# Power.net
KiCad netlist of a schematic drawn in Altium Designer
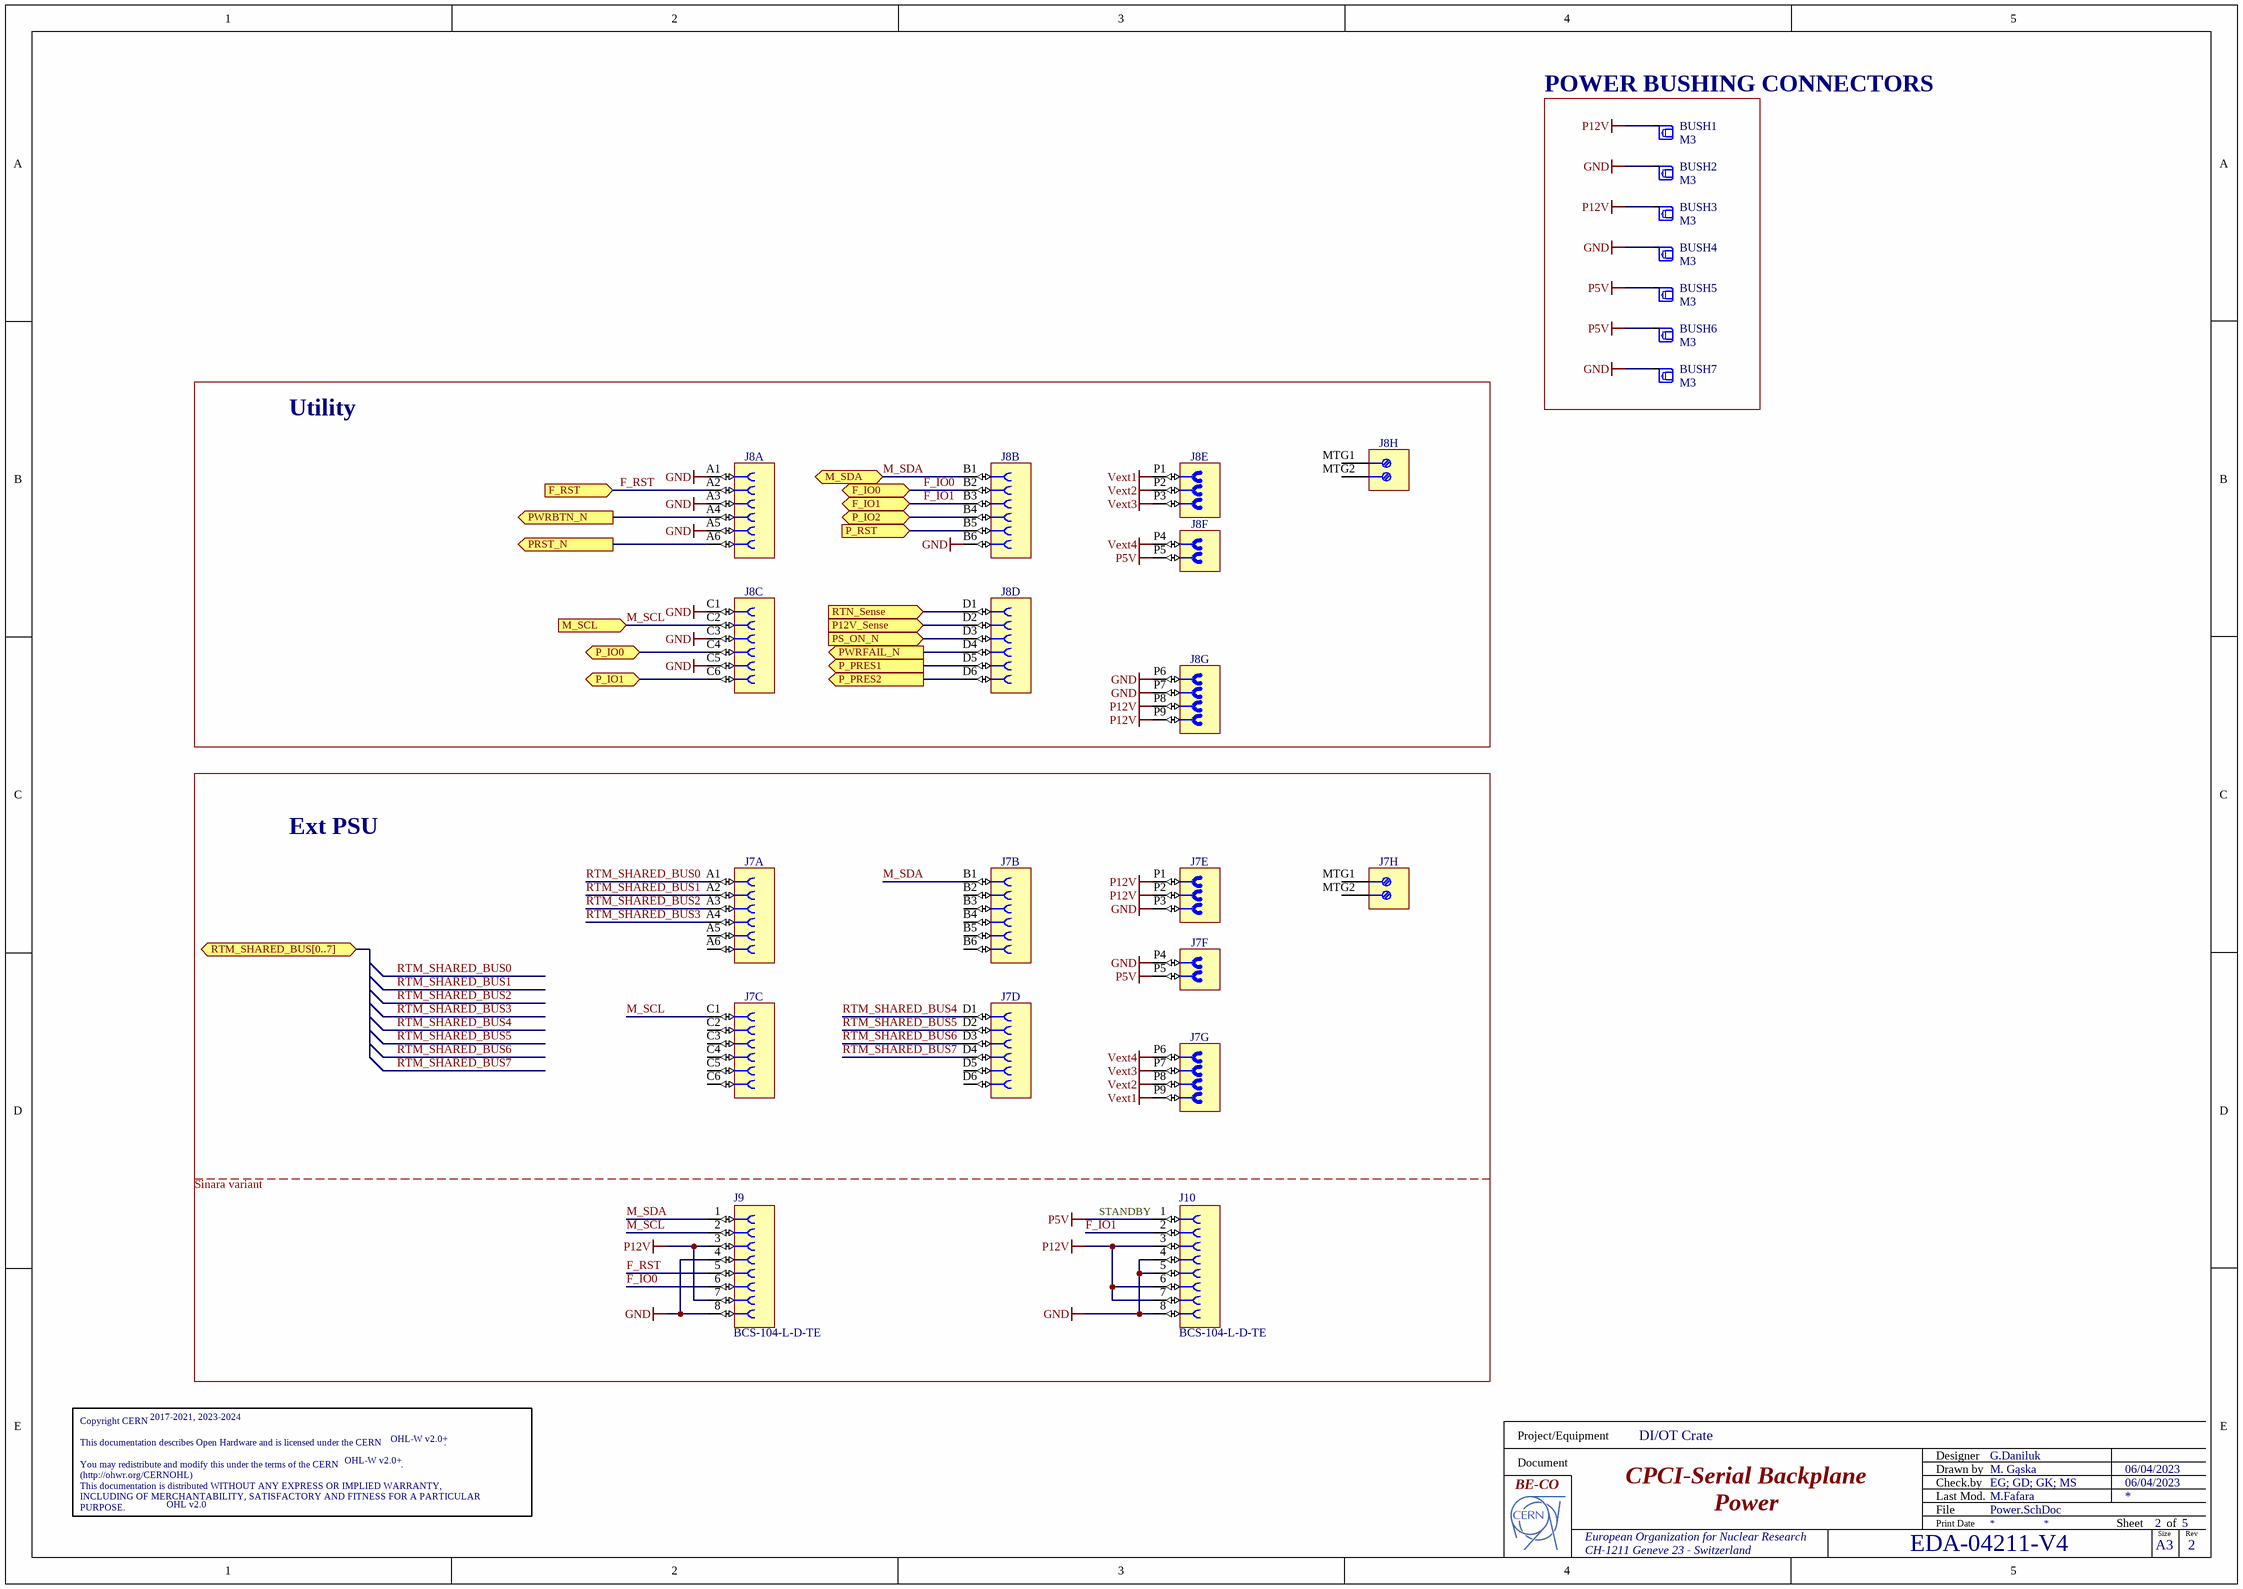
[diagram p0: Power.SchDoc]

(export (version "E")
  (design (tool "Eeschema 10.0.6"))
  (components
    (comp (ref "BUSH1")
      (value "M3")
      (footprint "WURTH_7461057")
      (description "Bush")
      (fields
        (field (name "PART NUMBER") "WURTH_7461057")
        (field (name "MANUFACTURER") "WURTH")
        (field (name "AUTHOR") "CERN DEM JLC")
      )
      (libsource (lib "Eletro-mechanical") (part "Bush"))
    )
    (comp (ref "BUSH2")
      (value "M3")
      (footprint "WURTH_7461057")
      (description "Bush")
      (fields
        (field (name "PART NUMBER") "WURTH_7461057")
        (field (name "MANUFACTURER") "WURTH")
        (field (name "AUTHOR") "CERN DEM JLC")
      )
      (libsource (lib "Eletro-mechanical") (part "Bush"))
    )
    (comp (ref "BUSH3")
      (value "M3")
      (footprint "WURTH_7461057")
      (description "Bush")
      (fields
        (field (name "PART NUMBER") "WURTH_7461057")
        (field (name "MANUFACTURER") "WURTH")
        (field (name "AUTHOR") "CERN DEM JLC")
      )
      (libsource (lib "Eletro-mechanical") (part "Bush"))
    )
    (comp (ref "BUSH4")
      (value "M3")
      (footprint "WURTH_7461057")
      (description "Bush")
      (fields
        (field (name "PART NUMBER") "WURTH_7461057")
        (field (name "MANUFACTURER") "WURTH")
        (field (name "AUTHOR") "CERN DEM JLC")
      )
      (libsource (lib "Eletro-mechanical") (part "Bush"))
    )
    (comp (ref "BUSH5")
      (value "M3")
      (footprint "WURTH_7461057")
      (description "Bush")
      (fields
        (field (name "PART NUMBER") "WURTH_7461057")
        (field (name "MANUFACTURER") "WURTH")
        (field (name "AUTHOR") "CERN DEM JLC")
      )
      (libsource (lib "Eletro-mechanical") (part "Bush"))
    )
    (comp (ref "BUSH6")
      (value "M3")
      (footprint "WURTH_7461057")
      (description "Bush")
      (fields
        (field (name "PART NUMBER") "WURTH_7461057")
        (field (name "MANUFACTURER") "WURTH")
        (field (name "AUTHOR") "CERN DEM JLC")
      )
      (libsource (lib "Eletro-mechanical") (part "Bush"))
    )
    (comp (ref "BUSH7")
      (value "M3")
      (footprint "WURTH_7461057")
      (description "Bush")
      (fields
        (field (name "PART NUMBER") "WURTH_7461057")
        (field (name "MANUFACTURER") "WURTH")
        (field (name "AUTHOR") "CERN DEM JLC")
      )
      (libsource (lib "Eletro-mechanical") (part "Bush"))
    )
    (comp (ref "J7")
      (value "PwrBlade")
      (footprint "AMPHENOL_51940-650")
      (description "Thru-Hole, Lead 3.43mm, PowerBlade Vertical Power Connector 3ACP 2P 24S 4DCP Contacts")
      (fields
        (field (name "PART NUMBER") "AMPHENOL_51940-650")
        (field (name "MANUFACTURER") "AMPHENOL")
        (field (name "AUTHOR") "CERN DEM HF")
      )
      (libsource (lib "Connectors") (part "AMPHENOL_51940-650"))
    )
    (comp (ref "J8")
      (value "PwrBlade")
      (footprint "AMPHENOL_51940-650")
      (description "Thru-Hole, Lead 3.43mm, PowerBlade Vertical Power Connector 3ACP 2P 24S 4DCP Contacts")
      (fields
        (field (name "PART NUMBER") "AMPHENOL_51940-650")
        (field (name "MANUFACTURER") "AMPHENOL")
        (field (name "AUTHOR") "CERN DEM HF")
      )
      (libsource (lib "Connectors") (part "AMPHENOL_51940-650"))
    )
    (comp (ref "J9")
      (value "BCS-104-L-D-TE")
      (footprint "SAMTEC_BCS-104-L-D-TE")
      (libsource (lib "TechnoSystem Workspace") (part "8 pin female"))
    )
    (comp (ref "J10")
      (value "BCS-104-L-D-TE")
      (footprint "SAMTEC_BCS-104-L-D-TE")
      (libsource (lib "TechnoSystem Workspace") (part "8 pin female"))
    )
  )
  (nets
    (net (code "1") (name "/F_IO0") (class "Default")
      (node (ref "J8") (pin "B2") (pinfunction "B2_B2") (pintype "bidirectional"))
      (node (ref "J9") (pin "6") (pinfunction "6_6") (pintype "bidirectional"))
    )
    (net (code "2") (name "/F_IO1") (class "Default")
      (node (ref "J10") (pin "2") (pinfunction "2_2") (pintype "bidirectional"))
      (node (ref "J8") (pin "B3") (pinfunction "B3_B3") (pintype "bidirectional"))
    )
    (net (code "3") (name "/F_RST") (class "Default")
      (node (ref "J8") (pin "A2") (pinfunction "A2_A2") (pintype "bidirectional"))
      (node (ref "J9") (pin "5") (pinfunction "5_5") (pintype "bidirectional"))
    )
    (net (code "4") (name "/M_SCL") (class "Default")
      (node (ref "J7") (pin "C1") (pinfunction "C1_C1") (pintype "bidirectional"))
      (node (ref "J8") (pin "C2") (pinfunction "C2_C2") (pintype "bidirectional"))
      (node (ref "J9") (pin "2") (pinfunction "2_2") (pintype "bidirectional"))
    )
    (net (code "5") (name "/M_SDA") (class "Default")
      (node (ref "J7") (pin "B1") (pinfunction "B1_B1") (pintype "bidirectional"))
      (node (ref "J8") (pin "B1") (pinfunction "B1_B1") (pintype "bidirectional"))
      (node (ref "J9") (pin "1") (pinfunction "1_1") (pintype "bidirectional"))
    )
    (net (code "6") (name "/P12V_Sense") (class "Default")
      (node (ref "J8") (pin "D2") (pinfunction "D2_D2") (pintype "bidirectional"))
    )
    (net (code "7") (name "/PRST_N") (class "Default")
      (node (ref "J8") (pin "A6") (pinfunction "A6_A6") (pintype "bidirectional"))
    )
    (net (code "8") (name "/PS_ON_N") (class "Default")
      (node (ref "J8") (pin "D3") (pinfunction "D3_D3") (pintype "bidirectional"))
    )
    (net (code "9") (name "/PWRBTN_N") (class "Default")
      (node (ref "J8") (pin "A4") (pinfunction "A4_A4") (pintype "bidirectional"))
    )
    (net (code "10") (name "/PWRFAIL_N") (class "Default")
      (node (ref "J8") (pin "D4") (pinfunction "D4_D4") (pintype "bidirectional"))
    )
    (net (code "11") (name "/P_IO0") (class "Default")
      (node (ref "J8") (pin "C4") (pinfunction "C4_C4") (pintype "bidirectional"))
    )
    (net (code "12") (name "/P_IO1") (class "Default")
      (node (ref "J8") (pin "C6") (pinfunction "C6_C6") (pintype "bidirectional"))
    )
    (net (code "13") (name "/P_IO2") (class "Default")
      (node (ref "J8") (pin "B4") (pinfunction "B4_B4") (pintype "bidirectional"))
    )
    (net (code "14") (name "/P_PRES1") (class "Default")
      (node (ref "J8") (pin "D5") (pinfunction "D5_D5") (pintype "bidirectional"))
    )
    (net (code "15") (name "/P_PRES2") (class "Default")
      (node (ref "J8") (pin "D6") (pinfunction "D6_D6") (pintype "bidirectional"))
    )
    (net (code "16") (name "/P_RST") (class "Default")
      (node (ref "J8") (pin "B5") (pinfunction "B5_B5") (pintype "bidirectional"))
    )
    (net (code "17") (name "/RTM_SHARED_BUS0") (class "Default")
      (node (ref "J7") (pin "A1") (pinfunction "A1_A1") (pintype "bidirectional"))
    )
    (net (code "18") (name "/RTM_SHARED_BUS1") (class "Default")
      (node (ref "J7") (pin "A2") (pinfunction "A2_A2") (pintype "bidirectional"))
    )
    (net (code "19") (name "/RTM_SHARED_BUS2") (class "Default")
      (node (ref "J7") (pin "A3") (pinfunction "A3_A3") (pintype "bidirectional"))
    )
    (net (code "20") (name "/RTM_SHARED_BUS3") (class "Default")
      (node (ref "J7") (pin "A4") (pinfunction "A4_A4") (pintype "bidirectional"))
    )
    (net (code "21") (name "/RTM_SHARED_BUS4") (class "Default")
      (node (ref "J7") (pin "D1") (pinfunction "D1_D1") (pintype "bidirectional"))
    )
    (net (code "22") (name "/RTM_SHARED_BUS5") (class "Default")
      (node (ref "J7") (pin "D2") (pinfunction "D2_D2") (pintype "bidirectional"))
    )
    (net (code "23") (name "/RTM_SHARED_BUS6") (class "Default")
      (node (ref "J7") (pin "D3") (pinfunction "D3_D3") (pintype "bidirectional"))
    )
    (net (code "24") (name "/RTM_SHARED_BUS7") (class "Default")
      (node (ref "J7") (pin "D4") (pinfunction "D4_D4") (pintype "bidirectional"))
    )
    (net (code "26") (name "/RTN_Sense") (class "Default")
      (node (ref "J8") (pin "D1") (pinfunction "D1_D1") (pintype "bidirectional"))
    )
    (net (code "27") (name "GND") (class "Default")
      (node (ref "BUSH2") (pin "1") (pinfunction "1_1") (pintype "bidirectional"))
      (node (ref "BUSH4") (pin "1") (pinfunction "1_1") (pintype "bidirectional"))
      (node (ref "BUSH7") (pin "1") (pinfunction "1_1") (pintype "bidirectional"))
      (node (ref "J10") (pin "4") (pinfunction "4_4") (pintype "bidirectional"))
      (node (ref "J10") (pin "5") (pinfunction "5_5") (pintype "bidirectional"))
      (node (ref "J10") (pin "8") (pinfunction "8_8") (pintype "bidirectional"))
      (node (ref "J7") (pin "P3") (pinfunction "P3_P3") (pintype "bidirectional"))
      (node (ref "J7") (pin "P4") (pinfunction "P4_P4") (pintype "bidirectional"))
      (node (ref "J8") (pin "A1") (pinfunction "A1_A1") (pintype "bidirectional"))
      (node (ref "J8") (pin "A3") (pinfunction "A3_A3") (pintype "bidirectional"))
      (node (ref "J8") (pin "A5") (pinfunction "A5_A5") (pintype "bidirectional"))
      (node (ref "J8") (pin "B6") (pinfunction "B6_B6") (pintype "bidirectional"))
      (node (ref "J8") (pin "C1") (pinfunction "C1_C1") (pintype "bidirectional"))
      (node (ref "J8") (pin "C3") (pinfunction "C3_C3") (pintype "bidirectional"))
      (node (ref "J8") (pin "C5") (pinfunction "C5_C5") (pintype "bidirectional"))
      (node (ref "J8") (pin "P6") (pinfunction "P6_P6") (pintype "bidirectional"))
      (node (ref "J8") (pin "P7") (pinfunction "P7_P7") (pintype "bidirectional"))
      (node (ref "J9") (pin "4") (pinfunction "4_4") (pintype "bidirectional"))
      (node (ref "J9") (pin "8") (pinfunction "8_8") (pintype "bidirectional"))
    )
    (net (code "28") (name "P5V") (class "Default")
      (node (ref "BUSH5") (pin "1") (pinfunction "1_1") (pintype "bidirectional"))
      (node (ref "BUSH6") (pin "1") (pinfunction "1_1") (pintype "bidirectional"))
      (node (ref "J10") (pin "1") (pinfunction "1_1") (pintype "bidirectional"))
      (node (ref "J7") (pin "P5") (pinfunction "P5_P5") (pintype "bidirectional"))
      (node (ref "J8") (pin "P5") (pinfunction "P5_P5") (pintype "bidirectional"))
    )
    (net (code "29") (name "P12V") (class "Default")
      (node (ref "BUSH1") (pin "1") (pinfunction "1_1") (pintype "bidirectional"))
      (node (ref "BUSH3") (pin "1") (pinfunction "1_1") (pintype "bidirectional"))
      (node (ref "J10") (pin "3") (pinfunction "3_3") (pintype "bidirectional"))
      (node (ref "J10") (pin "6") (pinfunction "6_6") (pintype "bidirectional"))
      (node (ref "J10") (pin "7") (pinfunction "7_7") (pintype "bidirectional"))
      (node (ref "J7") (pin "P1") (pinfunction "P1_P1") (pintype "bidirectional"))
      (node (ref "J7") (pin "P2") (pinfunction "P2_P2") (pintype "bidirectional"))
      (node (ref "J8") (pin "P8") (pinfunction "P8_P8") (pintype "bidirectional"))
      (node (ref "J8") (pin "P9") (pinfunction "P9_P9") (pintype "bidirectional"))
      (node (ref "J9") (pin "3") (pinfunction "3_3") (pintype "bidirectional"))
      (node (ref "J9") (pin "7") (pinfunction "7_7") (pintype "bidirectional"))
    )
    (net (code "30") (name "Vext1") (class "Default")
      (node (ref "J7") (pin "P9") (pinfunction "P9_P9") (pintype "bidirectional"))
      (node (ref "J8") (pin "P1") (pinfunction "P1_P1") (pintype "bidirectional"))
    )
    (net (code "31") (name "Vext2") (class "Default")
      (node (ref "J7") (pin "P8") (pinfunction "P8_P8") (pintype "bidirectional"))
      (node (ref "J8") (pin "P2") (pinfunction "P2_P2") (pintype "bidirectional"))
    )
    (net (code "32") (name "Vext3") (class "Default")
      (node (ref "J7") (pin "P7") (pinfunction "P7_P7") (pintype "bidirectional"))
      (node (ref "J8") (pin "P3") (pinfunction "P3_P3") (pintype "bidirectional"))
    )
    (net (code "33") (name "Vext4") (class "Default")
      (node (ref "J7") (pin "P6") (pinfunction "P6_P6") (pintype "bidirectional"))
      (node (ref "J8") (pin "P4") (pinfunction "P4_P4") (pintype "bidirectional"))
    )
    (net (code "34") (name "unconnected-(J7-PadA5)") (class "Default")
      (node (ref "J7") (pin "A5") (pinfunction "A5_A5") (pintype "bidirectional"))
    )
    (net (code "35") (name "unconnected-(J7-PadA6)") (class "Default")
      (node (ref "J7") (pin "A6") (pinfunction "A6_A6") (pintype "bidirectional"))
    )
    (net (code "36") (name "unconnected-(J7-PadB2)") (class "Default")
      (node (ref "J7") (pin "B2") (pinfunction "B2_B2") (pintype "bidirectional"))
    )
    (net (code "37") (name "unconnected-(J7-PadB3)") (class "Default")
      (node (ref "J7") (pin "B3") (pinfunction "B3_B3") (pintype "bidirectional"))
    )
    (net (code "38") (name "unconnected-(J7-PadB4)") (class "Default")
      (node (ref "J7") (pin "B4") (pinfunction "B4_B4") (pintype "bidirectional"))
    )
    (net (code "39") (name "unconnected-(J7-PadB5)") (class "Default")
      (node (ref "J7") (pin "B5") (pinfunction "B5_B5") (pintype "bidirectional"))
    )
    (net (code "40") (name "unconnected-(J7-PadB6)") (class "Default")
      (node (ref "J7") (pin "B6") (pinfunction "B6_B6") (pintype "bidirectional"))
    )
    (net (code "41") (name "unconnected-(J7-PadC2)") (class "Default")
      (node (ref "J7") (pin "C2") (pinfunction "C2_C2") (pintype "bidirectional"))
    )
    (net (code "42") (name "unconnected-(J7-PadC3)") (class "Default")
      (node (ref "J7") (pin "C3") (pinfunction "C3_C3") (pintype "bidirectional"))
    )
    (net (code "43") (name "unconnected-(J7-PadC4)") (class "Default")
      (node (ref "J7") (pin "C4") (pinfunction "C4_C4") (pintype "bidirectional"))
    )
    (net (code "44") (name "unconnected-(J7-PadC5)") (class "Default")
      (node (ref "J7") (pin "C5") (pinfunction "C5_C5") (pintype "bidirectional"))
    )
    (net (code "45") (name "unconnected-(J7-PadC6)") (class "Default")
      (node (ref "J7") (pin "C6") (pinfunction "C6_C6") (pintype "bidirectional"))
    )
    (net (code "46") (name "unconnected-(J7-PadD5)") (class "Default")
      (node (ref "J7") (pin "D5") (pinfunction "D5_D5") (pintype "bidirectional"))
    )
    (net (code "47") (name "unconnected-(J7-PadD6)") (class "Default")
      (node (ref "J7") (pin "D6") (pinfunction "D6_D6") (pintype "bidirectional"))
    )
    (net (code "48") (name "unconnected-(J7-PadMTG1)") (class "Default")
      (node (ref "J7") (pin "MTG1") (pinfunction "MTG1_MTG1") (pintype "passive"))
    )
    (net (code "49") (name "unconnected-(J7-PadMTG2)") (class "Default")
      (node (ref "J7") (pin "MTG2") (pinfunction "MTG2_MTG2") (pintype "passive"))
    )
    (net (code "50") (name "unconnected-(J8-PadMTG1)") (class "Default")
      (node (ref "J8") (pin "MTG1") (pinfunction "MTG1_MTG1") (pintype "passive"))
    )
    (net (code "51") (name "unconnected-(J8-PadMTG2)") (class "Default")
      (node (ref "J8") (pin "MTG2") (pinfunction "MTG2_MTG2") (pintype "passive"))
    )
  )
)
